# UltrazohmConnectors.net
KiCad netlist of a schematic drawn in Altium Designer
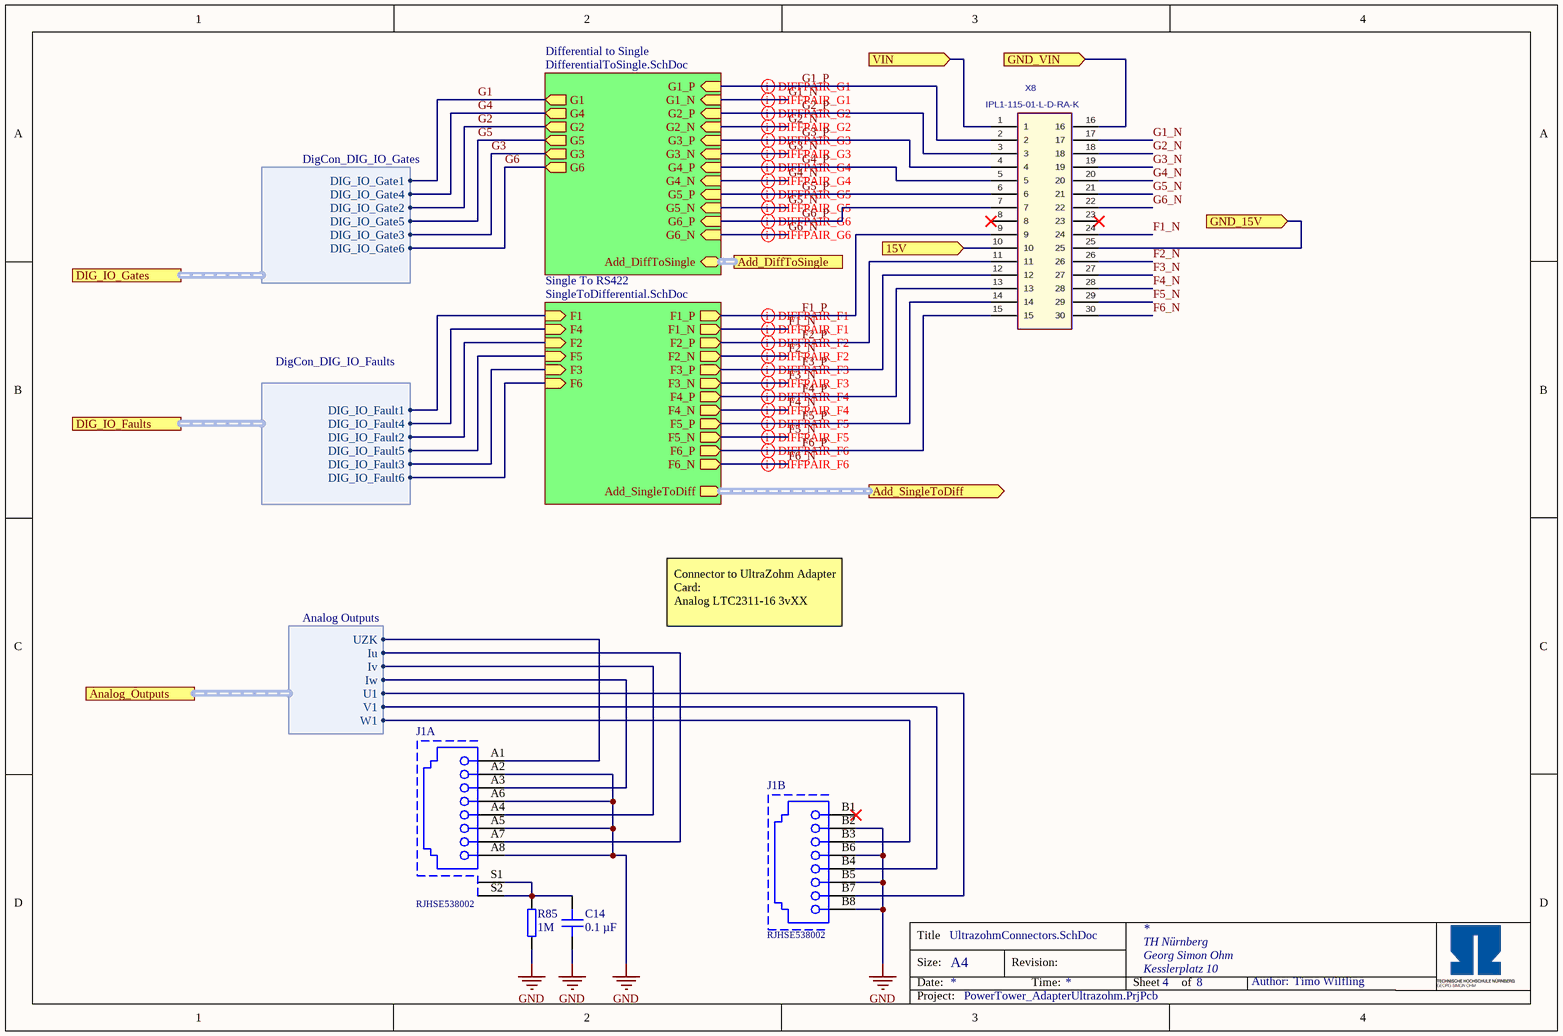
[diagram p0: UltrazohmConnectors.SchDoc]

(export (version "E")
  (design (tool "Eeschema 10.0.6"))
  (components
    (comp (ref "C14")
      (value "0.1 µF")
      (footprint "C_0805")
      (description "Capacitor 0805, 50 VDC, 0.1 µF, X7R")
      (fields
        (field (name "MANUFACTURER PART NUMBER") "C0805C104J5RECTU")
        (field (name "MANUFACTURER") "KEMET")
        (field (name "CREATED FROM") "MGremer")
      )
      (libsource (lib "user") (part "Capacitor"))
    )
    (comp (ref "J1")
      (value "RJHSE538002")
      (footprint "RJHSE-5380-02")
      (description "CAT5, RJ45 Connector, 1x2")
      (fields (field (name "MANUFACTURER") "Amphenol") (field (name "CREATED FROM") "MGremer"))
      (libsource (lib "user") (part "RJHSE-5380-02"))
    )
    (comp (ref "R85")
      (value "1M")
      (footprint "RES 0603_1608")
      (description "SMD resistor E24 series")
      (fields
        (field (name "MANUFACTURER PART NUMBER") "RK73B1JTTDD105J")
        (field (name "MANUFACTURER") "KOA Speer")
        (field (name "CREATED FROM") "MGremer")
      )
      (libsource (lib "user") (part "Resistor"))
    )
    (comp (ref "X8")
      (value "IPL1-115-01-L-D-RA-K")
      (footprint "IPL1-115-01-XX-D-RA")
      (description "Terminal Assembly, Double Row, Right Angle, Thru-Hole, 2.54 mm x 2.54 mm Pitch, 30 Pins")
      (fields (field (name "MANUFACTURER") "SAMTEC") (field (name "CREATED FROM") "TWendt"))
      (libsource (lib "user") (part "IPL1-115-01-XX-D-XX"))
    )
  )
  (nets
    (net (code "7") (name "/15V") (class "Default")
      (node (ref "X8") (pin "10") (pinfunction "10_10") (pintype "passive"))
    )
    (net (code "16") (name "/F1_N") (class "Default")
      (node (ref "X8") (pin "24") (pinfunction "24_24") (pintype "passive"))
    )
    (net (code "17") (name "/F1_P") (class "Default")
      (node (ref "X8") (pin "9") (pinfunction "9_9") (pintype "passive"))
    )
    (net (code "18") (name "/F2_N") (class "Default")
      (node (ref "X8") (pin "26") (pinfunction "26_26") (pintype "passive"))
    )
    (net (code "19") (name "/F2_P") (class "Default")
      (node (ref "X8") (pin "11") (pinfunction "11_11") (pintype "passive"))
    )
    (net (code "20") (name "/F3_N") (class "Default")
      (node (ref "X8") (pin "27") (pinfunction "27_27") (pintype "passive"))
    )
    (net (code "21") (name "/F3_P") (class "Default")
      (node (ref "X8") (pin "12") (pinfunction "12_12") (pintype "passive"))
    )
    (net (code "22") (name "/F4_N") (class "Default")
      (node (ref "X8") (pin "28") (pinfunction "28_28") (pintype "passive"))
    )
    (net (code "23") (name "/F4_P") (class "Default")
      (node (ref "X8") (pin "13") (pinfunction "13_13") (pintype "passive"))
    )
    (net (code "24") (name "/F5_N") (class "Default")
      (node (ref "X8") (pin "29") (pinfunction "29_29") (pintype "passive"))
    )
    (net (code "25") (name "/F5_P") (class "Default")
      (node (ref "X8") (pin "14") (pinfunction "14_14") (pintype "passive"))
    )
    (net (code "26") (name "/F6_N") (class "Default")
      (node (ref "X8") (pin "30") (pinfunction "30_30") (pintype "passive"))
    )
    (net (code "27") (name "/F6_P") (class "Default")
      (node (ref "X8") (pin "15") (pinfunction "15_15") (pintype "passive"))
    )
    (net (code "29") (name "/G1_N") (class "Default")
      (node (ref "X8") (pin "17") (pinfunction "17_17") (pintype "passive"))
    )
    (net (code "30") (name "/G1_P") (class "Default")
      (node (ref "X8") (pin "2") (pinfunction "2_2") (pintype "passive"))
    )
    (net (code "32") (name "/G2_N") (class "Default")
      (node (ref "X8") (pin "18") (pinfunction "18_18") (pintype "passive"))
    )
    (net (code "33") (name "/G2_P") (class "Default")
      (node (ref "X8") (pin "3") (pinfunction "3_3") (pintype "passive"))
    )
    (net (code "35") (name "/G3_N") (class "Default")
      (node (ref "X8") (pin "19") (pinfunction "19_19") (pintype "passive"))
    )
    (net (code "36") (name "/G3_P") (class "Default")
      (node (ref "X8") (pin "4") (pinfunction "4_4") (pintype "passive"))
    )
    (net (code "38") (name "/G4_N") (class "Default")
      (node (ref "X8") (pin "20") (pinfunction "20_20") (pintype "passive"))
    )
    (net (code "39") (name "/G4_P") (class "Default")
      (node (ref "X8") (pin "5") (pinfunction "5_5") (pintype "passive"))
    )
    (net (code "41") (name "/G5_N") (class "Default")
      (node (ref "X8") (pin "21") (pinfunction "21_21") (pintype "passive"))
    )
    (net (code "42") (name "/G5_P") (class "Default")
      (node (ref "X8") (pin "6") (pinfunction "6_6") (pintype "passive"))
    )
    (net (code "44") (name "/G6_N") (class "Default")
      (node (ref "X8") (pin "22") (pinfunction "22_22") (pintype "passive"))
    )
    (net (code "45") (name "/G6_P") (class "Default")
      (node (ref "X8") (pin "7") (pinfunction "7_7") (pintype "passive"))
    )
    (net (code "46") (name "/GND_15V") (class "Default")
      (node (ref "X8") (pin "25") (pinfunction "25_25") (pintype "passive"))
    )
    (net (code "47") (name "/GND_VIN") (class "Default")
      (node (ref "X8") (pin "16") (pinfunction "16_16") (pintype "passive"))
    )
    (net (code "48") (name "/Iu") (class "Default")
      (node (ref "J1") (pin "A7") (pinfunction "A7_A7") (pintype "passive"))
    )
    (net (code "49") (name "/Iv") (class "Default")
      (node (ref "J1") (pin "A4") (pinfunction "A4_A4") (pintype "passive"))
    )
    (net (code "50") (name "/Iw") (class "Default")
      (node (ref "J1") (pin "A3") (pinfunction "A3_A3") (pintype "passive"))
    )
    (net (code "51") (name "/U1") (class "Default")
      (node (ref "J1") (pin "B7") (pinfunction "B7_B7") (pintype "passive"))
    )
    (net (code "52") (name "/UZK") (class "Default")
      (node (ref "J1") (pin "A1") (pinfunction "A1_A1") (pintype "passive"))
    )
    (net (code "53") (name "/V1") (class "Default")
      (node (ref "J1") (pin "B4") (pinfunction "B4_B4") (pintype "passive"))
    )
    (net (code "54") (name "/VIN") (class "Default")
      (node (ref "X8") (pin "1") (pinfunction "1_1") (pintype "passive"))
    )
    (net (code "55") (name "/W1") (class "Default")
      (node (ref "J1") (pin "B3") (pinfunction "B3_B3") (pintype "passive"))
    )
    (net (code "59") (name "GND") (class "Default")
      (node (ref "C14") (pin "1") (pinfunction "1_1") (pintype "passive"))
      (node (ref "J1") (pin "A2") (pinfunction "A2_A2") (pintype "passive"))
      (node (ref "J1") (pin "A5") (pinfunction "A5_A5") (pintype "passive"))
      (node (ref "J1") (pin "A6") (pinfunction "A6_A6") (pintype "passive"))
      (node (ref "J1") (pin "A8") (pinfunction "A8_A8") (pintype "passive"))
      (node (ref "J1") (pin "B2") (pinfunction "B2_B2") (pintype "passive"))
      (node (ref "J1") (pin "B5") (pinfunction "B5_B5") (pintype "passive"))
      (node (ref "J1") (pin "B6") (pinfunction "B6_B6") (pintype "passive"))
      (node (ref "J1") (pin "B8") (pinfunction "B8_B8") (pintype "passive"))
      (node (ref "R85") (pin "1") (pinfunction "1_1") (pintype "passive"))
    )
    (net (code "60") (name "Net-(C14-Pad2)") (class "Default")
      (node (ref "C14") (pin "2") (pinfunction "2_2") (pintype "passive"))
      (node (ref "J1") (pin "S1") (pinfunction "S1_S1") (pintype "passive"))
      (node (ref "J1") (pin "S2") (pinfunction "S2_S2") (pintype "passive"))
      (node (ref "R85") (pin "2") (pinfunction "2_2") (pintype "passive"))
    )
    (net (code "61") (name "unconnected-(J1-PadB1)") (class "Default")
      (node (ref "J1") (pin "B1") (pinfunction "B1_B1") (pintype "passive+no_connect"))
    )
    (net (code "62") (name "unconnected-(X8-Pad8)") (class "Default")
      (node (ref "X8") (pin "8") (pinfunction "8_8") (pintype "passive+no_connect"))
    )
    (net (code "63") (name "unconnected-(X8-Pad23)") (class "Default")
      (node (ref "X8") (pin "23") (pinfunction "23_23") (pintype "passive+no_connect"))
    )
  )
)
